# MacSet-L-V2_0_0_1.net
KiCad netlist of a schematic drawn in Altium Designer
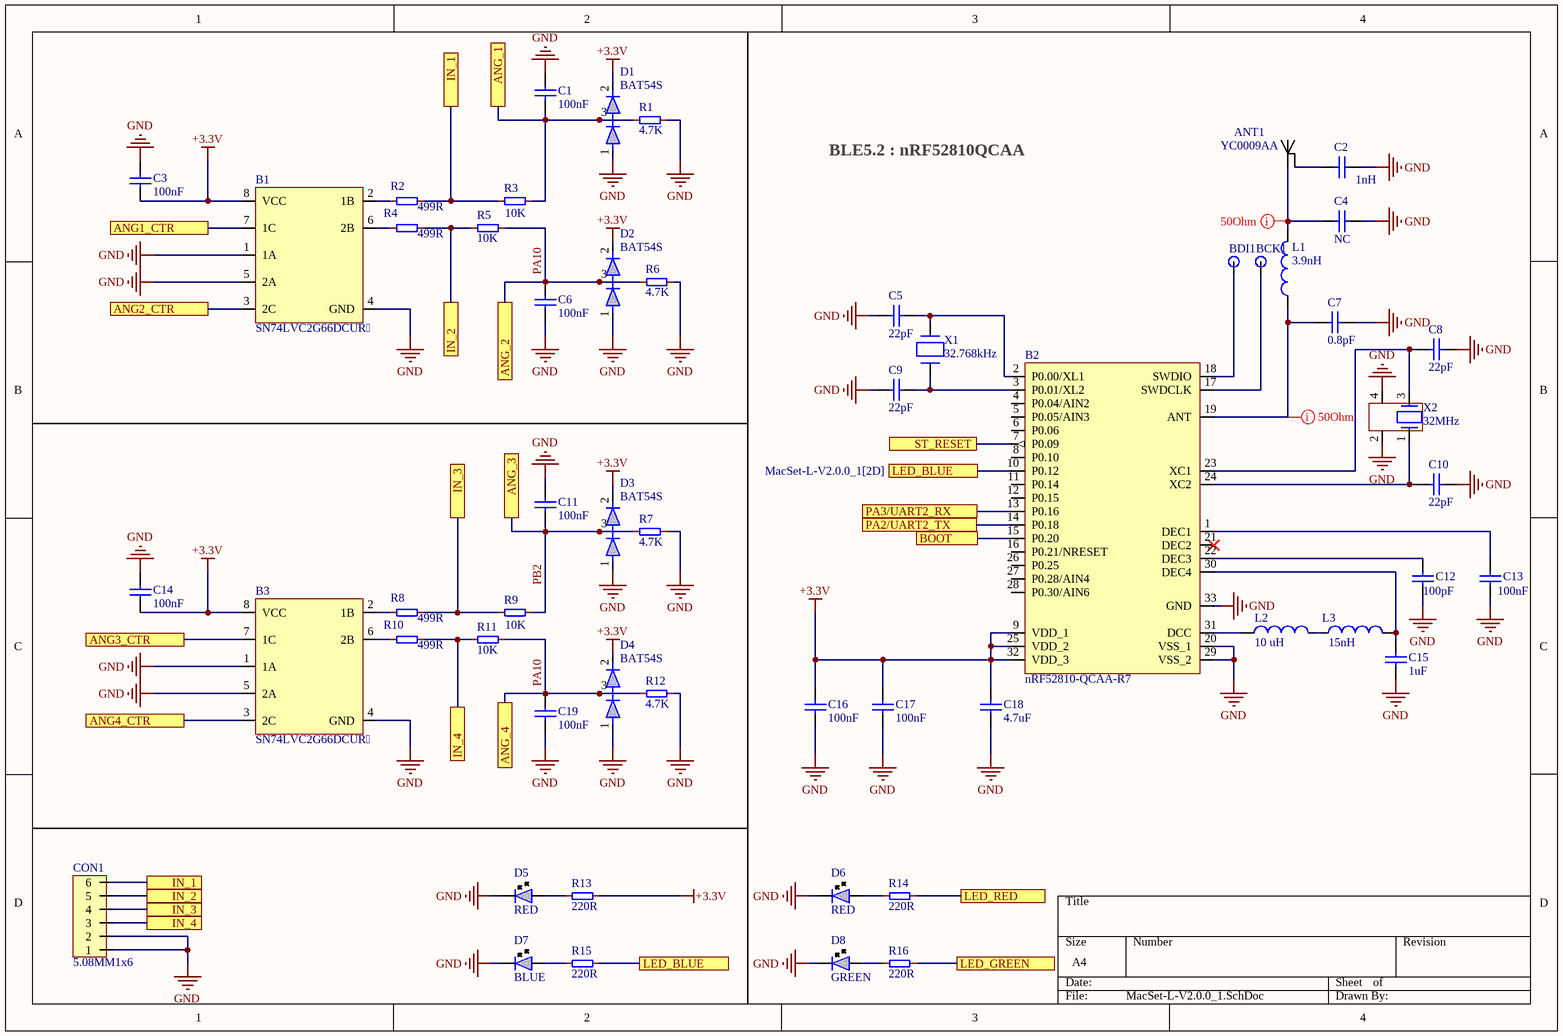
[diagram p0: MacSet-L-V2.0.0_1.SchDoc]

(export (version "E")
  (design (tool "Eeschema 10.0.6"))
  (components
    (comp (ref "ANT1")
      (value "YC0009AA")
      (footprint "YC009AA")
      (description "Antennas Embedded, 2400-2500 MHz, Wi-Fi (Bluetooth), Ceramic, -, -, SMD, 3.2 YCA009AA")
      (fields (field (name "MANUFACTURER") "Quectel"))
      (libsource (lib "macnman_2.0") (part "YC0009AA"))
    )
    (comp (ref "B1")
      (value "SN74LVC2G66DCUR")
      (footprint "SOP50P310X90-8N")
      (description "2-Channel, 1:1 Analog Switch with Low On-State Resistance")
      (fields
        (field (name "MANUFACTURER") "Texas Instruments")
        (field (name "MANUFACTURER_PART_NUMBER") "SN74LVC2G66DCUR")
      )
      (libsource (lib "macnman_2.0") (part "SN74LVC2G66DCUR"))
    )
    (comp (ref "B2")
      (value "nRF52810-QCAA-R7")
      (footprint "QFN50P500X500X95-33N")
      (fields (field (name "MANUFACTURER") "Nordic Semiconductor"))
      (libsource (lib "macnman_2.0") (part "nRF52810-QCAA-R7"))
    )
    (comp (ref "B3")
      (value "SN74LVC2G66DCUR")
      (footprint "SOP50P310X90-8N")
      (description "2-Channel, 1:1 Analog Switch with Low On-State Resistance")
      (fields
        (field (name "MANUFACTURER") "Texas Instruments")
        (field (name "MANUFACTURER_PART_NUMBER") "SN74LVC2G66DCUR")
      )
      (libsource (lib "macnman_2.0") (part "SN74LVC2G66DCUR"))
    )
    (comp (ref "BCK1")
      (value "-")
      (footprint "TH_Pad")
      (description "Through Hole pad 1mm 0.5mm Hole")
      (libsource (lib "macnman_2.0") (part "TH_PAD"))
    )
    (comp (ref "BDI1")
      (value "-")
      (footprint "TH_Pad")
      (description "Through Hole pad 1mm 0.5mm Hole")
      (libsource (lib "macnman_2.0") (part "TH_PAD"))
    )
    (comp (ref "C1")
      (value "100nF")
      (footprint "CAP0402")
      (description "Ceramic Capacitor C0G, NP0 0402 100nF 35V")
      (fields
        (field (name "MANUFACTURER_PART_NUMBER") "GRM155R61A104KA01J")
        (field (name "MANUFACTURER") "MURATA")
      )
      (libsource (lib "macnman_2.0") (part "Capa_0402"))
    )
    (comp (ref "C2")
      (value "1nH")
      (footprint "CAP0402")
      (description "Multilayer Ceramic Capacitors MLCC - SMD/SMT 50 V 22pF C0G 0402 5%")
      (fields
        (field (name "MANUFACTURER_PART_NUMBER") "LQG15HS1N0B02D")
        (field (name "MANUFACTURER") "Murata")
      )
      (libsource (lib "macnman_2.0") (part "Capa_0402"))
    )
    (comp (ref "C3")
      (value "100nF")
      (footprint "CAP0402")
      (description "Ceramic Capacitor C0G, NP0 0402 100nF 35V")
      (fields
        (field (name "MANUFACTURER_PART_NUMBER") "GRM155R61A104KA01J")
        (field (name "MANUFACTURER") "MURATA")
      )
      (libsource (lib "macnman_2.0") (part "Capa_0402"))
    )
    (comp (ref "C4") (value "NC") (footprint "CAP0402") (libsource (lib "macnman_2.0") (part "Capa_0402")))
    (comp (ref "C5")
      (value "22pF")
      (footprint "CAP0402")
      (description "Multilayer Ceramic Capacitors MLCC - SMD/SMT 50 V 22pF C0G 0402 5%")
      (fields
        (field (name "MANUFACTURER_PART_NUMBER") "GCM1555C1H220JA16D")
        (field (name "MANUFACTURER") "Murata")
      )
      (libsource (lib "macnman_2.0") (part "Capa_0402"))
    )
    (comp (ref "C6")
      (value "100nF")
      (footprint "CAP0402")
      (description "Ceramic Capacitor C0G, NP0 0402 100nF 35V")
      (fields
        (field (name "MANUFACTURER_PART_NUMBER") "GRM155R61A104KA01J")
        (field (name "MANUFACTURER") "MURATA")
      )
      (libsource (lib "macnman_2.0") (part "Capa_0402"))
    )
    (comp (ref "C7")
      (value "0.8pF")
      (footprint "CAP0402")
      (description "Ceramic Capacitor C0G, NP0 0402 0.8pF 50V")
      (fields
        (field (name "MANUFACTURER_PART_NUMBER") "CC0402BRNPO9BNR80")
        (field (name "MANUFACTURER") "YAGEO")
      )
      (libsource (lib "macnman_2.0") (part "Capa_0402"))
    )
    (comp (ref "C8")
      (value "22pF")
      (footprint "CAP0402")
      (description "Multilayer Ceramic Capacitors MLCC - SMD/SMT 50 V 22pF C0G 0402 5%")
      (fields
        (field (name "MANUFACTURER_PART_NUMBER") "GCM1555C1H220JA16D")
        (field (name "MANUFACTURER") "Murata")
      )
      (libsource (lib "macnman_2.0") (part "Capa_0402"))
    )
    (comp (ref "C9")
      (value "22pF")
      (footprint "CAP0402")
      (description "Multilayer Ceramic Capacitors MLCC - SMD/SMT 50 V 22pF C0G 0402 5%")
      (fields
        (field (name "MANUFACTURER_PART_NUMBER") "GCM1555C1H220JA16D")
        (field (name "MANUFACTURER") "Murata")
      )
      (libsource (lib "macnman_2.0") (part "Capa_0402"))
    )
    (comp (ref "C10")
      (value "22pF")
      (footprint "CAP0402")
      (description "Multilayer Ceramic Capacitors MLCC - SMD/SMT 50 V 22pF C0G 0402 5%")
      (fields
        (field (name "MANUFACTURER_PART_NUMBER") "GCM1555C1H220JA16D")
        (field (name "MANUFACTURER") "Murata")
      )
      (libsource (lib "macnman_2.0") (part "Capa_0402"))
    )
    (comp (ref "C11")
      (value "100nF")
      (footprint "CAP0402")
      (description "Ceramic Capacitor C0G, NP0 0402 100nF 35V")
      (fields
        (field (name "MANUFACTURER_PART_NUMBER") "GRM155R61A104KA01J")
        (field (name "MANUFACTURER") "MURATA")
      )
      (libsource (lib "macnman_2.0") (part "Capa_0402"))
    )
    (comp (ref "C12")
      (value "100pF")
      (footprint "CAP0402")
      (description "Ceramic Capacitor C0G, NP0 0402 100pF 50V")
      (fields
        (field (name "MANUFACTURER_PART_NUMBER") "GRM1555C1H101GA01D")
        (field (name "MANUFACTURER") "MURATA")
      )
      (libsource (lib "macnman_2.0") (part "Capa_0402"))
    )
    (comp (ref "C13")
      (value "100nF")
      (footprint "CAP0402")
      (description "Ceramic Capacitor X7R 0402 100nF 16V")
      (fields
        (field (name "MANUFACTURER_PART_NUMBER") "GRM155R71C104JA88D")
        (field (name "MANUFACTURER") "MURATA")
      )
      (libsource (lib "macnman_2.0") (part "Capa_0402"))
    )
    (comp (ref "C14")
      (value "100nF")
      (footprint "CAP0402")
      (description "Ceramic Capacitor C0G, NP0 0402 100nF 35V")
      (fields
        (field (name "MANUFACTURER_PART_NUMBER") "GRM155R61A104KA01J")
        (field (name "MANUFACTURER") "MURATA")
      )
      (libsource (lib "macnman_2.0") (part "Capa_0402"))
    )
    (comp (ref "C15")
      (value "1uF")
      (footprint "CAP0603")
      (description "MLCC - SMD/SMT 1 uF 16 VDC 10% 0603 X5R")
      (fields
        (field (name "MANUFACTURER_PART_NUMBER") "GRM188R61C105MA12D")
        (field (name "MANUFACTURER") "MURATA")
      )
      (libsource (lib "macnman_2.0") (part "Capa_0603"))
    )
    (comp (ref "C16")
      (value "100nF")
      (footprint "CAP0402")
      (description "Ceramic Capacitor X7R 0402 100nF 16V")
      (fields
        (field (name "MANUFACTURER_PART_NUMBER") "GRM155R71C104JA88D")
        (field (name "MANUFACTURER") "MURATA")
      )
      (libsource (lib "macnman_2.0") (part "Capa_0402"))
    )
    (comp (ref "C17")
      (value "100nF")
      (footprint "CAP0402")
      (description "Ceramic Capacitor X7R 0402 100nF 16V")
      (fields
        (field (name "MANUFACTURER_PART_NUMBER") "GRM155R71C104JA88D")
        (field (name "MANUFACTURER") "MURATA")
      )
      (libsource (lib "macnman_2.0") (part "Capa_0402"))
    )
    (comp (ref "C18")
      (value "4.7uF")
      (footprint "CAP0603")
      (description "MLCC - SMD/SMT 4.7 uF 16 VDC 10% 0603 X5R")
      (fields
        (field (name "MANUFACTURER_PART_NUMBER") "CL10A475KQ8NNNC")
        (field (name "MANUFACTURER") "Samsung Electro-Mechanics")
      )
      (libsource (lib "macnman_2.0") (part "Capa_0603"))
    )
    (comp (ref "C19")
      (value "100nF")
      (footprint "CAP0402")
      (description "Ceramic Capacitor C0G, NP0 0402 100nF 35V")
      (fields
        (field (name "MANUFACTURER_PART_NUMBER") "GRM155R61A104KA01J")
        (field (name "MANUFACTURER") "MURATA")
      )
      (libsource (lib "macnman_2.0") (part "Capa_0402"))
    )
    (comp (ref "CON1")
      (value "5.08MM1x6")
      (footprint "Screw Terminal Block 5.08x6")
      (description "5.08mm 1*6 Screw Terminal Block")
      (fields (field (name "MANUFACTURER") "XINYA"))
      (libsource (lib "macnman_2.0") (part "Screw Terminal Block 6x1 5.08mm"))
    )
    (comp (ref "D1")
      (value "BAT54S")
      (footprint "SOT23")
      (description "BAT54S Schottky Diodes & Rectifiers SS SHKY DIO 30V TR")
      (fields (field (name "MANUFACTURER_PART_NUMBER") "Nexperia") (field (name "MANUFACTURER") "BAT54S,235"))
      (libsource (lib "macnman_2.0") (part "BAT54SWT1G"))
    )
    (comp (ref "D2")
      (value "BAT54S")
      (footprint "SOT23")
      (description "BAT54S Schottky Diodes & Rectifiers SS SHKY DIO 30V TR")
      (fields (field (name "MANUFACTURER_PART_NUMBER") "Nexperia") (field (name "MANUFACTURER") "BAT54S,235"))
      (libsource (lib "macnman_2.0") (part "BAT54SWT1G"))
    )
    (comp (ref "D3")
      (value "BAT54S")
      (footprint "SOT23")
      (description "BAT54S Schottky Diodes & Rectifiers SS SHKY DIO 30V TR")
      (fields (field (name "MANUFACTURER_PART_NUMBER") "Nexperia") (field (name "MANUFACTURER") "BAT54S,235"))
      (libsource (lib "macnman_2.0") (part "BAT54SWT1G"))
    )
    (comp (ref "D4")
      (value "BAT54S")
      (footprint "SOT23")
      (description "BAT54S Schottky Diodes & Rectifiers SS SHKY DIO 30V TR")
      (fields (field (name "MANUFACTURER_PART_NUMBER") "Nexperia") (field (name "MANUFACTURER") "BAT54S,235"))
      (libsource (lib "macnman_2.0") (part "BAT54SWT1G"))
    )
    (comp (ref "D5")
      (value "RED")
      (footprint "LED_3MM")
      (description "LED 3MM Through Hole RED")
      (libsource (lib "macnman_2.0") (part "LED_3MM"))
    )
    (comp (ref "D6")
      (value "RED")
      (footprint "LED_3MM")
      (description "LED 3MM Through Hole RED")
      (libsource (lib "macnman_2.0") (part "LED_3MM"))
    )
    (comp (ref "D7")
      (value "BLUE")
      (footprint "LED_3MM")
      (description "LED 3MM Through Hole BLUE")
      (libsource (lib "macnman_2.0") (part "LED_3MM"))
    )
    (comp (ref "D8")
      (value "GREEN")
      (footprint "LED_3MM")
      (description "LED 3MM Through Hole GREEN")
      (libsource (lib "macnman_2.0") (part "LED_3MM"))
    )
    (comp (ref "L1")
      (value "3.9nH")
      (footprint "IND_0402")
      (description "3.9nH High frequency chip inductor ±5%  0402")
      (fields
        (field (name "MANUFACTURER_PART_NUMBER") "LQG15HS3N9B02D")
        (field (name "MANUFACTURER") "Murata")
      )
      (libsource (lib "macnman_2.0") (part "Inductor"))
    )
    (comp (ref "L2")
      (value "10 uH")
      (footprint "IND_0603")
      (description "250mA 10uH ±20% 90mΩ 0603 Inductors")
      (fields
        (field (name "MANUFACTURER_PART_NUMBER") "MLZ1608M100WT000")
        (field (name "MANUFACTURER") "TDK")
      )
      (libsource (lib "macnman_2.0") (part "MCD-01330"))
    )
    (comp (ref "L3")
      (value "15nH")
      (footprint "IND_0402")
      (description "400mA 15nH ±5% 350mΩ 0402 Inductors")
      (fields
        (field (name "MANUFACTURER_PART_NUMBER") "MLG1005S15NJT000")
        (field (name "MANUFACTURER") "Murata")
      )
      (libsource (lib "macnman_2.0") (part "MCD-01330"))
    )
    (comp (ref "R1")
      (value "4.7K")
      (footprint "RESC0402")
      (description "Thin Film Resistors - SMD 4.7Kohms 0.1% 0402 25ppm")
      (fields
        (field (name "MANUFACTURER_PART_NUMBER") "RT0402BRD074K7L")
        (field (name "MANUFACTURER") "YAGEO")
      )
      (libsource (lib "macnman_2.0") (part "RES_0402"))
    )
    (comp (ref "R2")
      (value "499R")
      (footprint "RESC0805")
      (description "Thin Film Resistors - SMD 499ohms 0.1% 25ppm")
      (fields
        (field (name "MANUFACTURER_PART_NUMBER") "TNPW0805499RBEEA")
        (field (name "MANUFACTURER") "Vishay")
      )
      (libsource (lib "macnman_2.0") (part "RES_0805"))
    )
    (comp (ref "R3")
      (value "10K")
      (footprint "RESC0402")
      (description "Thick Film Resistors - SMD 1/16watt 10Kohms 0.1% 0402 Commercial Use")
      (fields
        (field (name "MANUFACTURER_PART_NUMBER") "MCS04020D1002BE000")
        (field (name "MANUFACTURER") "Vishay")
      )
      (libsource (lib "macnman_2.0") (part "RES_0402"))
    )
    (comp (ref "R4")
      (value "499R")
      (footprint "RESC0805")
      (description "Thin Film Resistors - SMD 499ohms 0.1% 25ppm")
      (fields
        (field (name "MANUFACTURER_PART_NUMBER") "TNPW0805499RBEEA")
        (field (name "MANUFACTURER") "Vishay")
      )
      (libsource (lib "macnman_2.0") (part "RES_0805"))
    )
    (comp (ref "R5")
      (value "10K")
      (footprint "RESC0402")
      (description "Thick Film Resistors - SMD 1/16watt 10Kohms 0.1% 0402 Commercial Use")
      (fields
        (field (name "MANUFACTURER_PART_NUMBER") "MCS04020D1002BE000")
        (field (name "MANUFACTURER") "Vishay")
      )
      (libsource (lib "macnman_2.0") (part "RES_0402"))
    )
    (comp (ref "R6")
      (value "4.7K")
      (footprint "RESC0402")
      (description "Thin Film Resistors - SMD 4.7Kohms 0.1% 0402 25ppm")
      (fields
        (field (name "MANUFACTURER_PART_NUMBER") "RT0402BRD074K7L")
        (field (name "MANUFACTURER") "YAGEO")
      )
      (libsource (lib "macnman_2.0") (part "RES_0402"))
    )
    (comp (ref "R7")
      (value "4.7K")
      (footprint "RESC0402")
      (description "Thin Film Resistors - SMD 4.7Kohms 0.1% 0402 25ppm")
      (fields
        (field (name "MANUFACTURER_PART_NUMBER") "RT0402BRD074K7L")
        (field (name "MANUFACTURER") "YAGEO")
      )
      (libsource (lib "macnman_2.0") (part "RES_0402"))
    )
    (comp (ref "R8")
      (value "499R")
      (footprint "RESC0805")
      (description "Thin Film Resistors - SMD 499ohms 0.1% 25ppm")
      (fields
        (field (name "MANUFACTURER_PART_NUMBER") "TNPW0805499RBEEA")
        (field (name "MANUFACTURER") "Vishay")
      )
      (libsource (lib "macnman_2.0") (part "RES_0805"))
    )
    (comp (ref "R9")
      (value "10K")
      (footprint "RESC0402")
      (description "Thick Film Resistors - SMD 1/16watt 10Kohms 0.1% 0402 Commercial Use")
      (fields
        (field (name "MANUFACTURER_PART_NUMBER") "MCS04020D1002BE000")
        (field (name "MANUFACTURER") "Vishay")
      )
      (libsource (lib "macnman_2.0") (part "RES_0402"))
    )
    (comp (ref "R10")
      (value "499R")
      (footprint "RESC0805")
      (description "Thin Film Resistors - SMD 499ohms 0.1% 25ppm")
      (fields
        (field (name "MANUFACTURER_PART_NUMBER") "TNPW0805499RBEEA")
        (field (name "MANUFACTURER") "Vishay")
      )
      (libsource (lib "macnman_2.0") (part "RES_0805"))
    )
    (comp (ref "R11")
      (value "10K")
      (footprint "RESC0402")
      (description "Thick Film Resistors - SMD 1/16watt 10Kohms 0.1% 0402 Commercial Use")
      (fields
        (field (name "MANUFACTURER_PART_NUMBER") "MCS04020D1002BE000")
        (field (name "MANUFACTURER") "Vishay")
      )
      (libsource (lib "macnman_2.0") (part "RES_0402"))
    )
    (comp (ref "R12")
      (value "4.7K")
      (footprint "RESC0402")
      (description "Thin Film Resistors - SMD 4.7Kohms 0.1% 0402 25ppm")
      (fields
        (field (name "MANUFACTURER_PART_NUMBER") "RT0402BRD074K7L")
        (field (name "MANUFACTURER") "YAGEO")
      )
      (libsource (lib "macnman_2.0") (part "RES_0402"))
    )
    (comp (ref "R13")
      (value "220R")
      (footprint "RESC0402")
      (description "Thick Film Resistors - SMD 1/16watt 220R 0402 1% Commercial Use")
      (fields
        (field (name "MANUFACTURER_PART_NUMBER") "RC0402FR-07220RL")
        (field (name "MANUFACTURER") "Vishay")
      )
      (libsource (lib "macnman_2.0") (part "RES_0402"))
    )
    (comp (ref "R14")
      (value "220R")
      (footprint "RESC0402")
      (description "Thick Film Resistors - SMD 1/16watt 220R 0402 1% Commercial Use")
      (fields
        (field (name "MANUFACTURER_PART_NUMBER") "RC0402FR-07220RL")
        (field (name "MANUFACTURER") "Vishay")
      )
      (libsource (lib "macnman_2.0") (part "RES_0402"))
    )
    (comp (ref "R15")
      (value "220R")
      (footprint "RESC0402")
      (description "Thick Film Resistors - SMD 1/16watt 220R 0402 1% Commercial Use")
      (fields
        (field (name "MANUFACTURER_PART_NUMBER") "RC0402FR-07220RL")
        (field (name "MANUFACTURER") "Vishay")
      )
      (libsource (lib "macnman_2.0") (part "RES_0402"))
    )
    (comp (ref "R16")
      (value "220R")
      (footprint "RESC0402")
      (description "Thick Film Resistors - SMD 1/16watt 220R 0402 1% Commercial Use")
      (fields
        (field (name "MANUFACTURER_PART_NUMBER") "RC0402FR-07220RL")
        (field (name "MANUFACTURER") "Vishay")
      )
      (libsource (lib "macnman_2.0") (part "RES_0402"))
    )
    (comp (ref "X1")
      (value "32.768kHz")
      (footprint "OSC_3215")
      (description "Crystal Osc 3215 32.768kHz 12pF")
      (fields
        (field (name "MANUFACTURER_PART_NUMBER") "ECS-.327-12.5-34B-TR")
        (field (name "MANUFACTURER") "ECS")
      )
      (libsource (lib "macnman_2.0") (part "OSC_2012"))
    )
    (comp (ref "X2")
      (value "32MHz")
      (footprint "OSC_2016")
      (description "Crystal Osc 2016 32MHz 12pF  60R")
      (fields
        (field (name "MANUFACTURER_PART_NUMBER") "XRCGB32M000F1SADR0")
        (field (name "MANUFACTURER") "Murata")
      )
      (libsource (lib "macnman_2.0") (part "OSC_2016"))
    )
  )
  (nets
    (net (code "1") (name "+3.3V") (class "Default")
      (node (ref "B1") (pin "8") (pinfunction "VCC_8") (pintype "passive"))
      (node (ref "B2") (pin "25") (pinfunction "VDD_2_25") (pintype "passive"))
      (node (ref "B2") (pin "32") (pinfunction "VDD_3_32") (pintype "passive"))
      (node (ref "B2") (pin "9") (pinfunction "VDD_1_9") (pintype "passive"))
      (node (ref "B3") (pin "8") (pinfunction "VCC_8") (pintype "passive"))
      (node (ref "C14") (pin "2") (pinfunction "2_2") (pintype "passive"))
      (node (ref "C16") (pin "2") (pinfunction "2_2") (pintype "passive"))
      (node (ref "C17") (pin "2") (pinfunction "2_2") (pintype "passive"))
      (node (ref "C18") (pin "2") (pinfunction "2_2") (pintype "passive"))
      (node (ref "C3") (pin "2") (pinfunction "2_2") (pintype "passive"))
      (node (ref "D1") (pin "2") (pinfunction "2_2") (pintype "passive"))
      (node (ref "D2") (pin "2") (pinfunction "2_2") (pintype "passive"))
      (node (ref "D3") (pin "2") (pinfunction "2_2") (pintype "passive"))
      (node (ref "D4") (pin "2") (pinfunction "2_2") (pintype "passive"))
      (node (ref "R13") (pin "1") (pinfunction "1_1") (pintype "passive"))
    )
    (net (code "2") (name "/ANG1_CTR") (class "Default")
      (node (ref "B1") (pin "7") (pinfunction "1C_7") (pintype "passive"))
    )
    (net (code "3") (name "/ANG2_CTR") (class "Default")
      (node (ref "B1") (pin "3") (pinfunction "2C_3") (pintype "passive"))
    )
    (net (code "4") (name "/ANG3_CTR") (class "Default")
      (node (ref "B3") (pin "7") (pinfunction "1C_7") (pintype "passive"))
    )
    (net (code "5") (name "/ANG4_CTR") (class "Default")
      (node (ref "B3") (pin "3") (pinfunction "2C_3") (pintype "passive"))
    )
    (net (code "6") (name "/ANG_1") (class "Default")
      (node (ref "C1") (pin "1") (pinfunction "1_1") (pintype "passive"))
      (node (ref "D1") (pin "3") (pinfunction "3_3") (pintype "passive"))
      (node (ref "R1") (pin "2") (pinfunction "2_2") (pintype "passive"))
      (node (ref "R3") (pin "1") (pinfunction "1_1") (pintype "passive"))
    )
    (net (code "7") (name "/BOOT") (class "Default")
      (node (ref "B2") (pin "15") (pinfunction "P0.20_15") (pintype "passive"))
    )
    (net (code "8") (name "/IN_1") (class "Default")
      (node (ref "CON1") (pin "6") (pinfunction "6_6") (pintype "passive"))
      (node (ref "R2") (pin "2") (pinfunction "2_2") (pintype "passive"))
      (node (ref "R3") (pin "2") (pinfunction "2_2") (pintype "passive"))
    )
    (net (code "9") (name "/IN_2") (class "Default")
      (node (ref "CON1") (pin "5") (pinfunction "5_5") (pintype "passive"))
      (node (ref "R4") (pin "2") (pinfunction "2_2") (pintype "passive"))
      (node (ref "R5") (pin "2") (pinfunction "2_2") (pintype "passive"))
    )
    (net (code "10") (name "/IN_3") (class "Default")
      (node (ref "CON1") (pin "4") (pinfunction "4_4") (pintype "passive"))
      (node (ref "R8") (pin "2") (pinfunction "2_2") (pintype "passive"))
      (node (ref "R9") (pin "2") (pinfunction "2_2") (pintype "passive"))
    )
    (net (code "11") (name "/IN_4") (class "Default")
      (node (ref "CON1") (pin "3") (pinfunction "3_3") (pintype "passive"))
      (node (ref "R10") (pin "2") (pinfunction "2_2") (pintype "passive"))
      (node (ref "R11") (pin "2") (pinfunction "2_2") (pintype "passive"))
    )
    (net (code "12") (name "/LED_BLUE") (class "Default")
      (node (ref "B2") (pin "10") (pinfunction "P0.12_10") (pintype "passive"))
      (node (ref "R15") (pin "1") (pinfunction "1_1") (pintype "passive"))
    )
    (net (code "13") (name "/LED_GREEN") (class "Default")
      (node (ref "R16") (pin "1") (pinfunction "1_1") (pintype "passive"))
    )
    (net (code "14") (name "/LED_RED") (class "Default")
      (node (ref "R14") (pin "1") (pinfunction "1_1") (pintype "passive"))
    )
    (net (code "15") (name "/PA2{slash}UART2_TX") (class "Default")
      (node (ref "B2") (pin "14") (pinfunction "P0.18_14") (pintype "passive"))
    )
    (net (code "16") (name "/PA3{slash}UART2_RX") (class "Default")
      (node (ref "B2") (pin "13") (pinfunction "P0.16_13") (pintype "passive"))
    )
    (net (code "17") (name "/PA10") (class "Default")
      (node (ref "C19") (pin "2") (pinfunction "2_2") (pintype "passive"))
      (node (ref "C6") (pin "2") (pinfunction "2_2") (pintype "passive"))
      (node (ref "D2") (pin "3") (pinfunction "3_3") (pintype "passive"))
      (node (ref "D4") (pin "3") (pinfunction "3_3") (pintype "passive"))
      (node (ref "R11") (pin "1") (pinfunction "1_1") (pintype "passive"))
      (node (ref "R12") (pin "2") (pinfunction "2_2") (pintype "passive"))
      (node (ref "R5") (pin "1") (pinfunction "1_1") (pintype "passive"))
      (node (ref "R6") (pin "2") (pinfunction "2_2") (pintype "passive"))
    )
    (net (code "18") (name "/PB2") (class "Default")
      (node (ref "C11") (pin "1") (pinfunction "1_1") (pintype "passive"))
      (node (ref "D3") (pin "3") (pinfunction "3_3") (pintype "passive"))
      (node (ref "R7") (pin "2") (pinfunction "2_2") (pintype "passive"))
      (node (ref "R9") (pin "1") (pinfunction "1_1") (pintype "passive"))
    )
    (net (code "19") (name "/ST_RESET") (class "Default")
      (node (ref "B2") (pin "7") (pinfunction "P0.09_7") (pintype "output"))
    )
    (net (code "20") (name "GND") (class "Default")
      (node (ref "B1") (pin "1") (pinfunction "1A_1") (pintype "passive"))
      (node (ref "B1") (pin "4") (pinfunction "GND_4") (pintype "passive"))
      (node (ref "B1") (pin "5") (pinfunction "2A_5") (pintype "passive"))
      (node (ref "B2") (pin "20") (pinfunction "VSS_1_20") (pintype "passive"))
      (node (ref "B2") (pin "29") (pinfunction "VSS_2_29") (pintype "passive"))
      (node (ref "B2") (pin "33") (pinfunction "GND_33") (pintype "passive"))
      (node (ref "B3") (pin "1") (pinfunction "1A_1") (pintype "passive"))
      (node (ref "B3") (pin "4") (pinfunction "GND_4") (pintype "passive"))
      (node (ref "B3") (pin "5") (pinfunction "2A_5") (pintype "passive"))
      (node (ref "C1") (pin "2") (pinfunction "2_2") (pintype "passive"))
      (node (ref "C10") (pin "2") (pinfunction "2_2") (pintype "passive"))
      (node (ref "C11") (pin "2") (pinfunction "2_2") (pintype "passive"))
      (node (ref "C12") (pin "2") (pinfunction "2_2") (pintype "passive"))
      (node (ref "C13") (pin "2") (pinfunction "2_2") (pintype "passive"))
      (node (ref "C14") (pin "1") (pinfunction "1_1") (pintype "passive"))
      (node (ref "C15") (pin "1") (pinfunction "1_1") (pintype "passive"))
      (node (ref "C16") (pin "1") (pinfunction "1_1") (pintype "passive"))
      (node (ref "C17") (pin "1") (pinfunction "1_1") (pintype "passive"))
      (node (ref "C18") (pin "1") (pinfunction "1_1") (pintype "passive"))
      (node (ref "C19") (pin "1") (pinfunction "1_1") (pintype "passive"))
      (node (ref "C2") (pin "1") (pinfunction "1_1") (pintype "passive"))
      (node (ref "C3") (pin "1") (pinfunction "1_1") (pintype "passive"))
      (node (ref "C4") (pin "1") (pinfunction "1_1") (pintype "passive"))
      (node (ref "C5") (pin "1") (pinfunction "1_1") (pintype "passive"))
      (node (ref "C6") (pin "1") (pinfunction "1_1") (pintype "passive"))
      (node (ref "C7") (pin "1") (pinfunction "1_1") (pintype "passive"))
      (node (ref "C8") (pin "2") (pinfunction "2_2") (pintype "passive"))
      (node (ref "C9") (pin "1") (pinfunction "1_1") (pintype "passive"))
      (node (ref "CON1") (pin "1") (pinfunction "1_1") (pintype "passive"))
      (node (ref "CON1") (pin "2") (pinfunction "2_2") (pintype "passive"))
      (node (ref "D1") (pin "1") (pinfunction "1_1") (pintype "passive"))
      (node (ref "D2") (pin "1") (pinfunction "1_1") (pintype "passive"))
      (node (ref "D3") (pin "1") (pinfunction "1_1") (pintype "passive"))
      (node (ref "D4") (pin "1") (pinfunction "1_1") (pintype "passive"))
      (node (ref "D5") (pin "1") (pinfunction "K_1") (pintype "passive"))
      (node (ref "D6") (pin "1") (pinfunction "K_1") (pintype "passive"))
      (node (ref "D7") (pin "1") (pinfunction "K_1") (pintype "passive"))
      (node (ref "D8") (pin "1") (pinfunction "K_1") (pintype "passive"))
      (node (ref "R1") (pin "1") (pinfunction "1_1") (pintype "passive"))
      (node (ref "R12") (pin "1") (pinfunction "1_1") (pintype "passive"))
      (node (ref "R6") (pin "1") (pinfunction "1_1") (pintype "passive"))
      (node (ref "R7") (pin "1") (pinfunction "1_1") (pintype "passive"))
      (node (ref "X2") (pin "2") (pinfunction "2_2") (pintype "passive"))
      (node (ref "X2") (pin "4") (pinfunction "4_4") (pintype "passive"))
    )
    (net (code "21") (name "Net-(ANT1-Pad1)") (class "Default")
      (node (ref "ANT1") (pin "1") (pinfunction "1_1") (pintype "passive"))
      (node (ref "C4") (pin "2") (pinfunction "2_2") (pintype "passive"))
      (node (ref "L1") (pin "2") (pintype "passive"))
    )
    (net (code "22") (name "Net-(ANT1-Pad2)") (class "Default")
      (node (ref "ANT1") (pin "2") (pinfunction "2_2") (pintype "passive"))
      (node (ref "C2") (pin "2") (pinfunction "2_2") (pintype "passive"))
    )
    (net (code "23") (name "Net-(B1-1B)") (class "Default")
      (node (ref "B1") (pin "2") (pinfunction "1B_2") (pintype "passive"))
      (node (ref "R2") (pin "1") (pinfunction "1_1") (pintype "passive"))
    )
    (net (code "24") (name "Net-(B1-2B)") (class "Default")
      (node (ref "B1") (pin "6") (pinfunction "2B_6") (pintype "passive"))
      (node (ref "R4") (pin "1") (pinfunction "1_1") (pintype "passive"))
    )
    (net (code "25") (name "Net-(B2-ANT)") (class "Default")
      (node (ref "B2") (pin "19") (pinfunction "ANT_19") (pintype "passive"))
      (node (ref "C7") (pin "2") (pinfunction "2_2") (pintype "passive"))
      (node (ref "L1") (pin "1") (pintype "passive"))
    )
    (net (code "26") (name "Net-(B2-DCC)") (class "Default")
      (node (ref "B2") (pin "31") (pinfunction "DCC_31") (pintype "passive"))
      (node (ref "L2") (pin "1") (pinfunction "1_1") (pintype "passive"))
    )
    (net (code "27") (name "Net-(B2-DEC1)") (class "Default")
      (node (ref "B2") (pin "1") (pinfunction "DEC1_1") (pintype "passive"))
      (node (ref "C13") (pin "1") (pinfunction "1_1") (pintype "passive"))
    )
    (net (code "28") (name "Net-(B2-DEC3)") (class "Default")
      (node (ref "B2") (pin "22") (pinfunction "DEC3_22") (pintype "passive"))
      (node (ref "C12") (pin "1") (pinfunction "1_1") (pintype "passive"))
    )
    (net (code "29") (name "Net-(B2-DEC4)") (class "Default")
      (node (ref "B2") (pin "30") (pinfunction "DEC4_30") (pintype "passive"))
      (node (ref "C15") (pin "2") (pinfunction "2_2") (pintype "passive"))
      (node (ref "L3") (pin "2") (pinfunction "2_2") (pintype "passive"))
    )
    (net (code "30") (name "Net-(B2-P0.00{slash}XL1)") (class "Default")
      (node (ref "B2") (pin "2") (pinfunction "P0.00/XL1_2") (pintype "passive"))
      (node (ref "C5") (pin "2") (pinfunction "2_2") (pintype "passive"))
      (node (ref "X1") (pin "2") (pinfunction "X2_2") (pintype "passive"))
    )
    (net (code "31") (name "Net-(B2-P0.01{slash}XL2)") (class "Default")
      (node (ref "B2") (pin "3") (pinfunction "P0.01/XL2_3") (pintype "passive"))
      (node (ref "C9") (pin "2") (pinfunction "2_2") (pintype "passive"))
      (node (ref "X1") (pin "1") (pinfunction "X1_1") (pintype "passive"))
    )
    (net (code "32") (name "Net-(B2-SWDCLK)") (class "Default")
      (node (ref "B2") (pin "17") (pinfunction "SWDCLK_17") (pintype "passive"))
      (node (ref "BCK1") (pin "1") (pinfunction "1_1") (pintype "passive"))
    )
    (net (code "33") (name "Net-(B2-SWDIO)") (class "Default")
      (node (ref "B2") (pin "18") (pinfunction "SWDIO_18") (pintype "passive"))
      (node (ref "BDI1") (pin "1") (pinfunction "1_1") (pintype "passive"))
    )
    (net (code "34") (name "Net-(B2-XC1)") (class "Default")
      (node (ref "B2") (pin "23") (pinfunction "XC1_23") (pintype "passive"))
      (node (ref "C8") (pin "1") (pinfunction "1_1") (pintype "passive"))
      (node (ref "X2") (pin "3") (pinfunction "3_3") (pintype "passive"))
    )
    (net (code "35") (name "Net-(B2-XC2)") (class "Default")
      (node (ref "B2") (pin "24") (pinfunction "XC2_24") (pintype "passive"))
      (node (ref "C10") (pin "1") (pinfunction "1_1") (pintype "passive"))
      (node (ref "X2") (pin "1") (pinfunction "1_1") (pintype "passive"))
    )
    (net (code "36") (name "Net-(B3-1B)") (class "Default")
      (node (ref "B3") (pin "2") (pinfunction "1B_2") (pintype "passive"))
      (node (ref "R8") (pin "1") (pinfunction "1_1") (pintype "passive"))
    )
    (net (code "37") (name "Net-(B3-2B)") (class "Default")
      (node (ref "B3") (pin "6") (pinfunction "2B_6") (pintype "passive"))
      (node (ref "R10") (pin "1") (pinfunction "1_1") (pintype "passive"))
    )
    (net (code "38") (name "Net-(D5-A)") (class "Default")
      (node (ref "D5") (pin "2") (pinfunction "A_2") (pintype "passive"))
      (node (ref "R13") (pin "2") (pinfunction "2_2") (pintype "passive"))
    )
    (net (code "39") (name "Net-(D6-A)") (class "Default")
      (node (ref "D6") (pin "2") (pinfunction "A_2") (pintype "passive"))
      (node (ref "R14") (pin "2") (pinfunction "2_2") (pintype "passive"))
    )
    (net (code "40") (name "Net-(D7-A)") (class "Default")
      (node (ref "D7") (pin "2") (pinfunction "A_2") (pintype "passive"))
      (node (ref "R15") (pin "2") (pinfunction "2_2") (pintype "passive"))
    )
    (net (code "41") (name "Net-(D8-A)") (class "Default")
      (node (ref "D8") (pin "2") (pinfunction "A_2") (pintype "passive"))
      (node (ref "R16") (pin "2") (pinfunction "2_2") (pintype "passive"))
    )
    (net (code "42") (name "Net-(L2-Pad2)") (class "Default")
      (node (ref "L2") (pin "2") (pinfunction "2_2") (pintype "passive"))
      (node (ref "L3") (pin "1") (pinfunction "1_1") (pintype "passive"))
    )
    (net (code "43") (name "unconnected-(B2-DEC2-Pad21)") (class "Default")
      (node (ref "B2") (pin "21") (pinfunction "DEC2_21") (pintype "passive+no_connect"))
    )
    (net (code "44") (name "unconnected-(B2-P0.04{slash}AIN2-Pad4)") (class "Default")
      (node (ref "B2") (pin "4") (pinfunction "P0.04/AIN2_4") (pintype "passive"))
    )
    (net (code "45") (name "unconnected-(B2-P0.05{slash}AIN3-Pad5)") (class "Default")
      (node (ref "B2") (pin "5") (pinfunction "P0.05/AIN3_5") (pintype "passive"))
    )
    (net (code "46") (name "unconnected-(B2-P0.06-Pad6)") (class "Default")
      (node (ref "B2") (pin "6") (pinfunction "P0.06_6") (pintype "passive"))
    )
    (net (code "47") (name "unconnected-(B2-P0.10-Pad8)") (class "Default")
      (node (ref "B2") (pin "8") (pinfunction "P0.10_8") (pintype "passive"))
    )
    (net (code "48") (name "unconnected-(B2-P0.14-Pad11)") (class "Default")
      (node (ref "B2") (pin "11") (pinfunction "P0.14_11") (pintype "passive"))
    )
    (net (code "49") (name "unconnected-(B2-P0.15-Pad12)") (class "Default")
      (node (ref "B2") (pin "12") (pinfunction "P0.15_12") (pintype "passive"))
    )
    (net (code "50") (name "unconnected-(B2-P0.21{slash}NRESET-Pad16)") (class "Default")
      (node (ref "B2") (pin "16") (pinfunction "P0.21/NRESET_16") (pintype "passive"))
    )
    (net (code "51") (name "unconnected-(B2-P0.25-Pad26)") (class "Default")
      (node (ref "B2") (pin "26") (pinfunction "P0.25_26") (pintype "passive"))
    )
    (net (code "52") (name "unconnected-(B2-P0.28{slash}AIN4-Pad27)") (class "Default")
      (node (ref "B2") (pin "27") (pinfunction "P0.28/AIN4_27") (pintype "passive"))
    )
    (net (code "53") (name "unconnected-(B2-P0.30{slash}AIN6-Pad28)") (class "Default")
      (node (ref "B2") (pin "28") (pinfunction "P0.30/AIN6_28") (pintype "passive"))
    )
  )
)
